# auto.net
KiCad netlist of a schematic drawn in Altium Designer
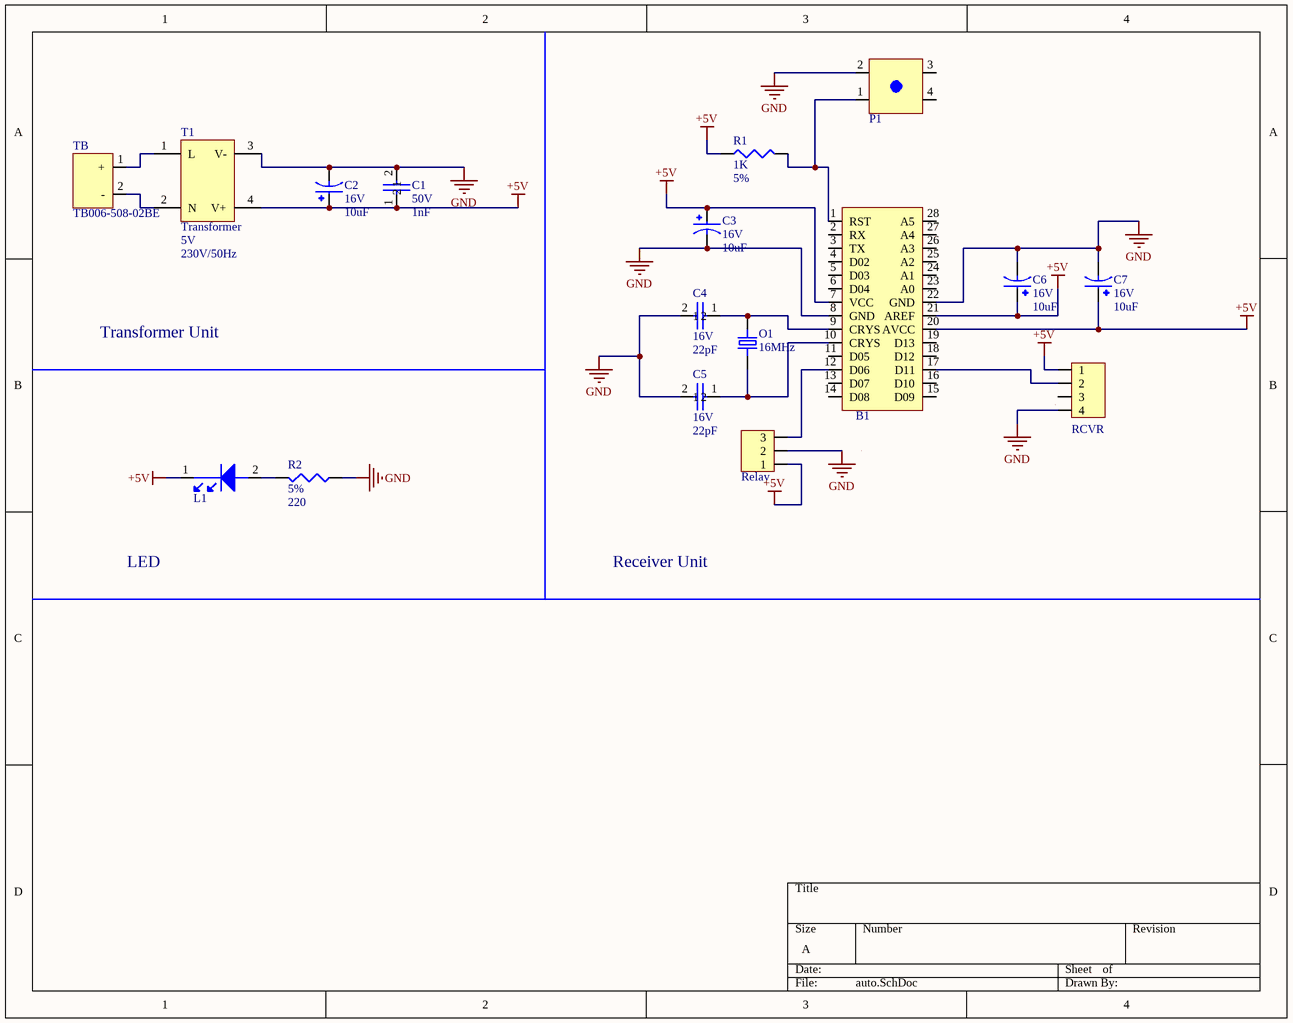
[diagram p0: auto.SchDoc]

(export (version "E")
  (design (tool "Eeschema 10.0.6"))
  (components
    (comp (ref "B1")
      (value "1-2199298-8")
      (footprint "FP-1-2199298-9-MFG")
      (description "IC Socket")
      (fields (field (name "MANUFACTURER") "TE Connectivity"))
      (libsource (lib "auto") (part "1-2199298-8"))
    )
    (comp (ref "C1")
      (value "K102K15X7RF5TL2")
      (footprint "10uF_Capacitor")
      (fields
        (field (name "MANUFACTURER") "Vishay BCcomponents")
        (field (name "VOLTAGE") "50V")
        (field (name "CAPACITANCE") "1nF")
      )
      (libsource (lib "auto") (part "K102K15X7RF5TL2"))
    )
    (comp (ref "C2")
      (value "EEA-GA1C100")
      (footprint "10uF_Capacitor")
      (fields
        (field (name "MANUFACTURER") "Panasonic")
        (field (name "VOLTAGE") "16V")
        (field (name "CAPACITANCE") "10uF")
      )
      (libsource (lib "auto") (part "EEA-GA1C100"))
    )
    (comp (ref "C3")
      (value "EEA-GA1C100")
      (footprint "10uF_Capacitor")
      (fields
        (field (name "MANUFACTURER") "Panasonic")
        (field (name "VOLTAGE") "16V")
        (field (name "CAPACITANCE") "10uF")
      )
      (libsource (lib "") (part "EEA-GA1C100_2"))
    )
    (comp (ref "C4")
      (value "S220K25SL0N63L6R")
      (footprint "10uF_Capacitor")
      (fields
        (field (name "MANUFACTURER") "Vishay BCcomponents")
        (field (name "VOLTAGE") "16V")
        (field (name "CAPACITANCE") "22pF")
      )
      (libsource (lib "auto") (part "S220K25SL0N63L6R"))
    )
    (comp (ref "C5")
      (value "S220K25SL0N63L6R")
      (footprint "10uF_Capacitor")
      (fields
        (field (name "MANUFACTURER") "Vishay BCcomponents")
        (field (name "VOLTAGE") "16V")
        (field (name "CAPACITANCE") "22pF")
      )
      (libsource (lib "auto") (part "S220K25SL0N63L6R"))
    )
    (comp (ref "C6")
      (value "EEA-GA1C100")
      (footprint "10uF_Capacitor")
      (fields
        (field (name "MANUFACTURER") "Panasonic")
        (field (name "VOLTAGE") "16V")
        (field (name "CAPACITANCE") "10uF")
      )
      (libsource (lib "") (part "EEA-GA1C100_1"))
    )
    (comp (ref "C7")
      (value "EEA-GA1C100")
      (footprint "10uF_Capacitor")
      (fields
        (field (name "MANUFACTURER") "Panasonic")
        (field (name "VOLTAGE") "16V")
        (field (name "CAPACITANCE") "10uF")
      )
      (libsource (lib "") (part "EEA-GA1C100_1"))
    )
    (comp (ref "L1")
      (value "WP7113SRD/J4")
      (footprint "LEDRD254W57D500H1070")
      (description "LED Uni-Color SB. Red 660nm 2-Pin T-1 3/4 Bulk")
      (fields (field (name "MANUFACTURER") "Kingbright"))
      (libsource (lib "auto") (part "WP7113SRD/J4"))
    )
    (comp (ref "O1")
      (value "16MHz")
      (footprint "Oscillator")
      (fields (field (name "MP") "ECS-160-20-4") (field (name "Comment") "ECS-160-20-4_1"))
      (libsource (lib "auto") (part "ECS-160-20-4_1"))
    )
    (comp (ref "P1")
      (value "COM-00097")
      (footprint "P_button")
      (description "CONN HEADER SMD 28POS 0.8MM")
      (fields (field (name "MANUFACTURER") "SparkFun"))
      (libsource (lib "auto") (part "COM-00097"))
    )
    (comp (ref "R1")
      (value "CFM12JT1K00")
      (footprint "Resister")
      (description "Fixed Resistor, Carbon Film, 0.5W, 1000ohm, 350V, 5% +/-Tol, -400,0ppm/Cel, Through Hole Mount")
      (fields
        (field (name "MANUFACTURER") "Stackpole Electronics")
        (field (name "POWER") "500mW")
        (field (name "RESISTANCE") "1K")
        (field (name "TOLERANCE") "5%")
      )
      (libsource (lib "auto") (part "CFM12JT1K00"))
    )
    (comp (ref "R2")
      (value "CFM12JT220R")
      (footprint "Resister")
      (description "Fixed Resistor, Carbon Film, 0.5W, 220ohm, 350V, 5% +/-Tol, -400,0ppm/Cel, Through Hole Mount")
      (fields
        (field (name "MANUFACTURER") "Stackpole Electronics")
        (field (name "POWER") "500mW")
        (field (name "TOLERANCE") "5%")
        (field (name "RESISTANCE") "220")
      )
      (libsource (lib "auto") (part "CFM12JT220R"))
    )
    (comp (ref "RCVR")
      (value "61300411121")
      (footprint "61300411121")
      (fields (field (name "MANUFACTURER") "Wurth Electronics"))
      (libsource (lib "auto") (part "61300411121"))
    )
    (comp (ref "Relay")
      (value "61300311121")
      (footprint "Female")
      (fields (field (name "MANUFACTURER") "Wurth Electronics"))
      (libsource (lib "auto") (part "61300311121"))
    )
    (comp (ref "T1")
      (value "Transformer")
      (footprint "Hilink")
      (description "5V 0.6A 90VAC~265VAC 120V~350V 3W AC-DC 73% Plugin Power Modules ROHS")
      (fields (field (name "OUTPUT VOLTAGE") "5V") (field (name "INPUT VOLATGE") "230V/50Hz"))
      (libsource (lib "auto") (part "Transformer"))
    )
    (comp (ref "TB")
      (value "TB006-508-02BE")
      (footprint "terminalbox")
      (description "Barrier Strip Terminal Block")
      (fields (field (name "MANUFACTURER") "CUI Devices"))
      (libsource (lib "auto") (part "TB006-508-02BE"))
    )
  )
  (nets
    (net (code "1") (name "+5V") (class "Default")
      (node (ref "B1") (pin "20") (pinfunction "AVCC_20") (pintype "power_in"))
      (node (ref "B1") (pin "21") (pinfunction "AREF_21") (pintype "passive"))
      (node (ref "B1") (pin "7") (pinfunction "VCC_7") (pintype "power_in"))
      (node (ref "C1") (pin "1") (pinfunction "1_1") (pintype "passive"))
      (node (ref "C2") (pin "1") (pinfunction "1_1") (pintype "passive"))
      (node (ref "C3") (pin "1") (pinfunction "1_1") (pintype "passive"))
      (node (ref "C6") (pin "1") (pinfunction "1_1") (pintype "passive"))
      (node (ref "C7") (pin "1") (pinfunction "1_1") (pintype "passive"))
      (node (ref "L1") (pin "1") (pinfunction "1_1") (pintype "passive"))
      (node (ref "R1") (pin "1") (pinfunction "1_1") (pintype "passive"))
      (node (ref "RCVR") (pin "1") (pinfunction "1_1") (pintype "passive"))
      (node (ref "Relay") (pin "1") (pinfunction "1_1") (pintype "passive"))
      (node (ref "T1") (pin "4") (pinfunction "V+_4") (pintype "passive"))
    )
    (net (code "2") (name "GND") (class "Default")
      (node (ref "B1") (pin "22") (pinfunction "GND_22") (pintype "power_in"))
      (node (ref "B1") (pin "8") (pinfunction "GND_8") (pintype "power_in"))
      (node (ref "C1") (pin "2") (pinfunction "2_2") (pintype "passive"))
      (node (ref "C2") (pin "2") (pinfunction "2_2") (pintype "passive"))
      (node (ref "C3") (pin "2") (pinfunction "2_2") (pintype "passive"))
      (node (ref "C4") (pin "2") (pinfunction "2_2") (pintype "passive"))
      (node (ref "C5") (pin "2") (pinfunction "2_2") (pintype "passive"))
      (node (ref "C6") (pin "2") (pinfunction "2_2") (pintype "passive"))
      (node (ref "C7") (pin "2") (pinfunction "2_2") (pintype "passive"))
      (node (ref "P1") (pin "2") (pinfunction "3_2") (pintype "passive"))
      (node (ref "R2") (pin "2") (pinfunction "2_2") (pintype "passive"))
      (node (ref "RCVR") (pin "4") (pinfunction "4_4") (pintype "passive"))
      (node (ref "Relay") (pin "2") (pinfunction "2_2") (pintype "passive"))
      (node (ref "T1") (pin "3") (pinfunction "V-_3") (pintype "passive"))
    )
    (net (code "3") (name "Net-(B1-CRYS-Pad9)") (class "Default")
      (node (ref "B1") (pin "9") (pinfunction "CRYS_9") (pintype "passive"))
      (node (ref "C4") (pin "1") (pinfunction "1_1") (pintype "passive"))
      (node (ref "O1") (pin "1") (pinfunction "1_1") (pintype "passive"))
    )
    (net (code "4") (name "Net-(B1-CRYS-Pad10)") (class "Default")
      (node (ref "B1") (pin "10") (pinfunction "CRYS_10") (pintype "passive"))
      (node (ref "C5") (pin "1") (pinfunction "1_1") (pintype "passive"))
      (node (ref "O1") (pin "2") (pinfunction "2_2") (pintype "passive"))
    )
    (net (code "5") (name "Net-(B1-D06)") (class "Default")
      (node (ref "B1") (pin "12") (pinfunction "D06_12") (pintype "bidirectional"))
      (node (ref "Relay") (pin "3") (pinfunction "3_3") (pintype "passive"))
    )
    (net (code "6") (name "Net-(B1-D11)") (class "Default")
      (node (ref "B1") (pin "17") (pinfunction "D11_17") (pintype "bidirectional"))
      (node (ref "RCVR") (pin "2") (pinfunction "2_2") (pintype "passive"))
    )
    (net (code "7") (name "Net-(B1-RST)") (class "Default")
      (node (ref "B1") (pin "1") (pinfunction "RST_1") (pintype "passive"))
      (node (ref "P1") (pin "1") (pinfunction "4_1") (pintype "passive"))
      (node (ref "R1") (pin "2") (pinfunction "2_2") (pintype "passive"))
    )
    (net (code "8") (name "Net-(L1-Pad2)") (class "Default")
      (node (ref "L1") (pin "2") (pinfunction "2_2") (pintype "passive"))
      (node (ref "R2") (pin "1") (pinfunction "1_1") (pintype "passive"))
    )
    (net (code "9") (name "Net-(T1-L)") (class "Default")
      (node (ref "T1") (pin "1") (pinfunction "L_1") (pintype "passive"))
      (node (ref "TB") (pin "1") (pinfunction "+_1") (pintype "passive"))
    )
    (net (code "10") (name "Net-(T1-N)") (class "Default")
      (node (ref "T1") (pin "2") (pinfunction "N_2") (pintype "passive"))
      (node (ref "TB") (pin "2") (pinfunction "-_2") (pintype "passive"))
    )
    (net (code "11") (name "unconnected-(B1-A0-Pad23)") (class "Default")
      (node (ref "B1") (pin "23") (pinfunction "A0_23") (pintype "passive"))
    )
    (net (code "12") (name "unconnected-(B1-A1-Pad24)") (class "Default")
      (node (ref "B1") (pin "24") (pinfunction "A1_24") (pintype "passive"))
    )
    (net (code "13") (name "unconnected-(B1-A2-Pad25)") (class "Default")
      (node (ref "B1") (pin "25") (pinfunction "A2_25") (pintype "passive"))
    )
    (net (code "14") (name "unconnected-(B1-A3-Pad26)") (class "Default")
      (node (ref "B1") (pin "26") (pinfunction "A3_26") (pintype "passive"))
    )
    (net (code "15") (name "unconnected-(B1-A4-Pad27)") (class "Default")
      (node (ref "B1") (pin "27") (pinfunction "A4_27") (pintype "passive"))
    )
    (net (code "16") (name "unconnected-(B1-A5-Pad28)") (class "Default")
      (node (ref "B1") (pin "28") (pinfunction "A5_28") (pintype "passive"))
    )
    (net (code "17") (name "unconnected-(B1-D02-Pad4)") (class "Default")
      (node (ref "B1") (pin "4") (pinfunction "D02_4") (pintype "bidirectional"))
    )
    (net (code "18") (name "unconnected-(B1-D03-Pad5)") (class "Default")
      (node (ref "B1") (pin "5") (pinfunction "D03_5") (pintype "bidirectional"))
    )
    (net (code "19") (name "unconnected-(B1-D04-Pad6)") (class "Default")
      (node (ref "B1") (pin "6") (pinfunction "D04_6") (pintype "bidirectional"))
    )
    (net (code "20") (name "unconnected-(B1-D05-Pad11)") (class "Default")
      (node (ref "B1") (pin "11") (pinfunction "D05_11") (pintype "bidirectional"))
    )
    (net (code "21") (name "unconnected-(B1-D07-Pad13)") (class "Default")
      (node (ref "B1") (pin "13") (pinfunction "D07_13") (pintype "bidirectional"))
    )
    (net (code "22") (name "unconnected-(B1-D08-Pad14)") (class "Default")
      (node (ref "B1") (pin "14") (pinfunction "D08_14") (pintype "bidirectional"))
    )
    (net (code "23") (name "unconnected-(B1-D09-Pad15)") (class "Default")
      (node (ref "B1") (pin "15") (pinfunction "D09_15") (pintype "bidirectional"))
    )
    (net (code "24") (name "unconnected-(B1-D10-Pad16)") (class "Default")
      (node (ref "B1") (pin "16") (pinfunction "D10_16") (pintype "bidirectional"))
    )
    (net (code "25") (name "unconnected-(B1-D12-Pad18)") (class "Default")
      (node (ref "B1") (pin "18") (pinfunction "D12_18") (pintype "bidirectional"))
    )
    (net (code "26") (name "unconnected-(B1-D13-Pad19)") (class "Default")
      (node (ref "B1") (pin "19") (pinfunction "D13_19") (pintype "bidirectional"))
    )
    (net (code "27") (name "unconnected-(B1-RX-Pad2)") (class "Default")
      (node (ref "B1") (pin "2") (pinfunction "RX_2") (pintype "bidirectional"))
    )
    (net (code "28") (name "unconnected-(B1-TX-Pad3)") (class "Default")
      (node (ref "B1") (pin "3") (pinfunction "TX_3") (pintype "bidirectional"))
    )
    (net (code "29") (name "unconnected-(P1-Pad3)") (class "Default")
      (node (ref "P1") (pin "3") (pinfunction "3_3") (pintype "passive"))
    )
    (net (code "30") (name "unconnected-(P1-Pad4)") (class "Default")
      (node (ref "P1") (pin "4") (pinfunction "4_4") (pintype "passive"))
    )
    (net (code "31") (name "unconnected-(RCVR-Pad3)") (class "Default")
      (node (ref "RCVR") (pin "3") (pinfunction "3_3") (pintype "passive"))
    )
  )
)
